# PowerPanel_SMD.net
KiCad netlist of a schematic drawn in EAGLE
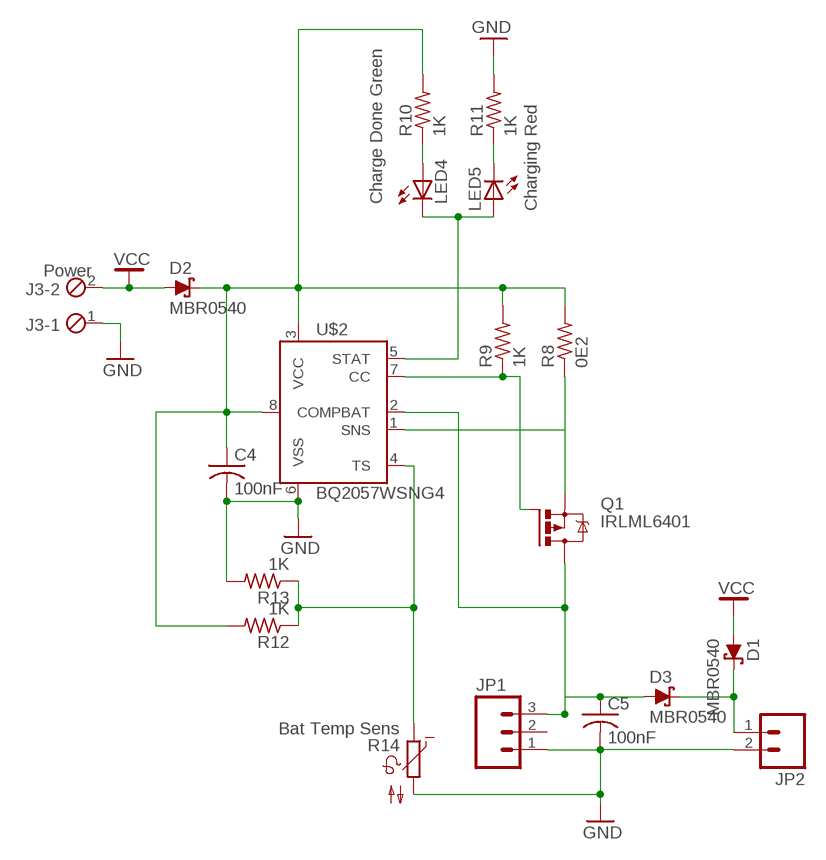
[diagram p0: schematic, sheet 1]

(export (version "E")
  (design (tool "Eeschema 10.0.6"))
  (components
    (comp (ref "C4")
      (value "100nF")
      (footprint "eagle-import:C0805K")
      (libsource (lib "eagle-import") (part "C-USC0805K"))
    )
    (comp (ref "C5")
      (value "100nF")
      (footprint "eagle-import:C0805K")
      (libsource (lib "eagle-import") (part "C-USC0805K"))
    )
    (comp (ref "D1")
      (value "MBR0540")
      (footprint "eagle-import:SOD123")
      (libsource (lib "eagle-import") (part "MBR0540"))
    )
    (comp (ref "D2")
      (value "MBR0540")
      (footprint "eagle-import:SOD123")
      (libsource (lib "eagle-import") (part "MBR0540"))
    )
    (comp (ref "D3")
      (value "MBR0540")
      (footprint "eagle-import:SOD123")
      (libsource (lib "eagle-import") (part "MBR0540"))
    )
    (comp (ref "J3")
      (value "Power")
      (footprint "eagle-import:796689-2")
      (libsource (lib "eagle-import") (part "796689-2"))
    )
    (comp (ref "JP1")
      (value "M03LONGPADS")
      (footprint "eagle-import:1X03_LONGPADS")
      (libsource (lib "eagle-import") (part "M03LONGPADS"))
    )
    (comp (ref "JP2")
      (value "M02PTH3")
      (footprint "eagle-import:1X02_LONGPADS")
      (libsource (lib "eagle-import") (part "M02PTH3"))
    )
    (comp (ref "LED4")
      (value "Charge Done Green")
      (footprint "eagle-import:CHIPLED_0805")
      (libsource (lib "eagle-import") (part "LEDCHIPLED_0805"))
    )
    (comp (ref "LED5")
      (value "Charging Red")
      (footprint "eagle-import:CHIPLED_0805")
      (libsource (lib "eagle-import") (part "LEDCHIPLED_0805"))
    )
    (comp (ref "Q1")
      (value "IRLML6401")
      (footprint "eagle-import:MICRO3")
      (libsource (lib "eagle-import") (part "IRLML5203"))
    )
    (comp (ref "R8")
      (value "0E2")
      (footprint "eagle-import:M1206")
      (libsource (lib "eagle-import") (part "R-US_M1206"))
    )
    (comp (ref "R9")
      (value "1K")
      (footprint "eagle-import:R0805")
      (libsource (lib "eagle-import") (part "R-US_R0805"))
    )
    (comp (ref "R10")
      (value "1K")
      (footprint "eagle-import:R0805")
      (libsource (lib "eagle-import") (part "R-US_R0805"))
    )
    (comp (ref "R11")
      (value "1K")
      (footprint "eagle-import:R0805")
      (libsource (lib "eagle-import") (part "R-US_R0805"))
    )
    (comp (ref "R12")
      (value "1K")
      (footprint "eagle-import:R0805")
      (libsource (lib "eagle-import") (part "R-US_R0805"))
    )
    (comp (ref "R13")
      (value "1K")
      (footprint "eagle-import:R0805")
      (libsource (lib "eagle-import") (part "R-US_R0805"))
    )
    (comp (ref "R14")
      (value "Bat Temp Sens")
      (footprint "eagle-import:P640")
      (libsource (lib "eagle-import") (part "NTC640"))
    )
    (comp (ref "U$2")
      (value "BQ2057WSNG4")
      (footprint "eagle-import:D_R-PDSO-G8")
      (libsource (lib "eagle-import") (part "BQ2057WSNG4"))
    )
  )
  (nets
    (net (code "1") (name "GND") (class "Default")
      (node (ref "C4") (pin "2") (pinfunction "2_2") (pintype "passive"))
      (node (ref "C5") (pin "2") (pinfunction "2_2") (pintype "passive"))
      (node (ref "J3") (pin "1") (pinfunction "1_1") (pintype "passive"))
      (node (ref "JP1") (pin "1") (pinfunction "1_1") (pintype "passive"))
      (node (ref "JP2") (pin "2") (pinfunction "2_2") (pintype "passive"))
      (node (ref "R11") (pin "2") (pinfunction "2_2") (pintype "passive"))
      (node (ref "R13") (pin "2") (pinfunction "2_2") (pintype "passive"))
      (node (ref "R14") (pin "2") (pinfunction "2_2") (pintype "passive"))
      (node (ref "U$2") (pin "6") (pinfunction "VSS_6") (pintype "power_in"))
    )
    (net (code "2") (name "Net-(D1-PadC)") (class "Default")
      (node (ref "D1") (pin "C") (pinfunction "C_C") (pintype "passive"))
      (node (ref "D3") (pin "C") (pinfunction "C_C") (pintype "passive"))
      (node (ref "JP2") (pin "1") (pinfunction "1_1") (pintype "passive"))
    )
    (net (code "3") (name "Net-(LED4-PadA)") (class "Default")
      (node (ref "LED4") (pin "A") (pinfunction "A_A") (pintype "passive"))
      (node (ref "R10") (pin "1") (pinfunction "1_1") (pintype "passive"))
    )
    (net (code "4") (name "Net-(LED5-PadC)") (class "Default")
      (node (ref "LED5") (pin "C") (pinfunction "C_C") (pintype "passive"))
      (node (ref "R11") (pin "1") (pinfunction "1_1") (pintype "passive"))
    )
    (net (code "5") (name "Net-(Q1-D)") (class "Default")
      (node (ref "C5") (pin "1") (pinfunction "1_1") (pintype "passive"))
      (node (ref "D3") (pin "A") (pinfunction "A_A") (pintype "passive"))
      (node (ref "JP1") (pin "3") (pinfunction "3_3") (pintype "passive"))
      (node (ref "Q1") (pin "3") (pinfunction "D_3") (pintype "passive"))
      (node (ref "U$2") (pin "2") (pinfunction "BAT_2") (pintype "input"))
    )
    (net (code "6") (name "Net-(Q1-G)") (class "Default")
      (node (ref "Q1") (pin "1") (pinfunction "G_1") (pintype "passive"))
      (node (ref "R9") (pin "1") (pinfunction "1_1") (pintype "passive"))
      (node (ref "U$2") (pin "7") (pinfunction "CC_7") (pintype "output"))
    )
    (net (code "7") (name "Net-(Q1-S)") (class "Default")
      (node (ref "Q1") (pin "2") (pinfunction "S_2") (pintype "passive"))
      (node (ref "R8") (pin "1") (pinfunction "1_1") (pintype "passive"))
      (node (ref "U$2") (pin "1") (pinfunction "SNS_1") (pintype "input"))
    )
    (net (code "8") (name "Net-(U$2-COMP)") (class "Default")
      (node (ref "C4") (pin "1") (pinfunction "1_1") (pintype "passive"))
      (node (ref "D2") (pin "C") (pinfunction "C_C") (pintype "passive"))
      (node (ref "R10") (pin "2") (pinfunction "2_2") (pintype "passive"))
      (node (ref "R12") (pin "2") (pinfunction "2_2") (pintype "passive"))
      (node (ref "R8") (pin "2") (pinfunction "2_2") (pintype "passive"))
      (node (ref "R9") (pin "2") (pinfunction "2_2") (pintype "passive"))
      (node (ref "U$2") (pin "3") (pinfunction "VCC_3") (pintype "input"))
      (node (ref "U$2") (pin "8") (pinfunction "COMP_8") (pintype "input"))
    )
    (net (code "9") (name "Net-(U$2-STAT)") (class "Default")
      (node (ref "LED4") (pin "C") (pinfunction "C_C") (pintype "passive"))
      (node (ref "LED5") (pin "A") (pinfunction "A_A") (pintype "passive"))
      (node (ref "U$2") (pin "5") (pinfunction "STAT_5") (pintype "output"))
    )
    (net (code "10") (name "Net-(U$2-TS)") (class "Default")
      (node (ref "R12") (pin "1") (pinfunction "1_1") (pintype "passive"))
      (node (ref "R13") (pin "1") (pinfunction "1_1") (pintype "passive"))
      (node (ref "R14") (pin "1") (pinfunction "1_1") (pintype "passive"))
      (node (ref "U$2") (pin "4") (pinfunction "TS_4") (pintype "input"))
    )
    (net (code "11") (name "VCC") (class "Default")
      (node (ref "D1") (pin "A") (pinfunction "A_A") (pintype "passive"))
      (node (ref "D2") (pin "A") (pinfunction "A_A") (pintype "passive"))
      (node (ref "J3") (pin "2") (pinfunction "1_2") (pintype "passive"))
    )
    (net (code "12") (name "unconnected-(JP1-Pad2)") (class "Default")
      (node (ref "JP1") (pin "2") (pinfunction "2_2") (pintype "passive"))
    )
  )
)
